# LcsNodes-Extension-BreadBoard-B_00_01.net
KiCad netlist of a schematic drawn in EasyEDA
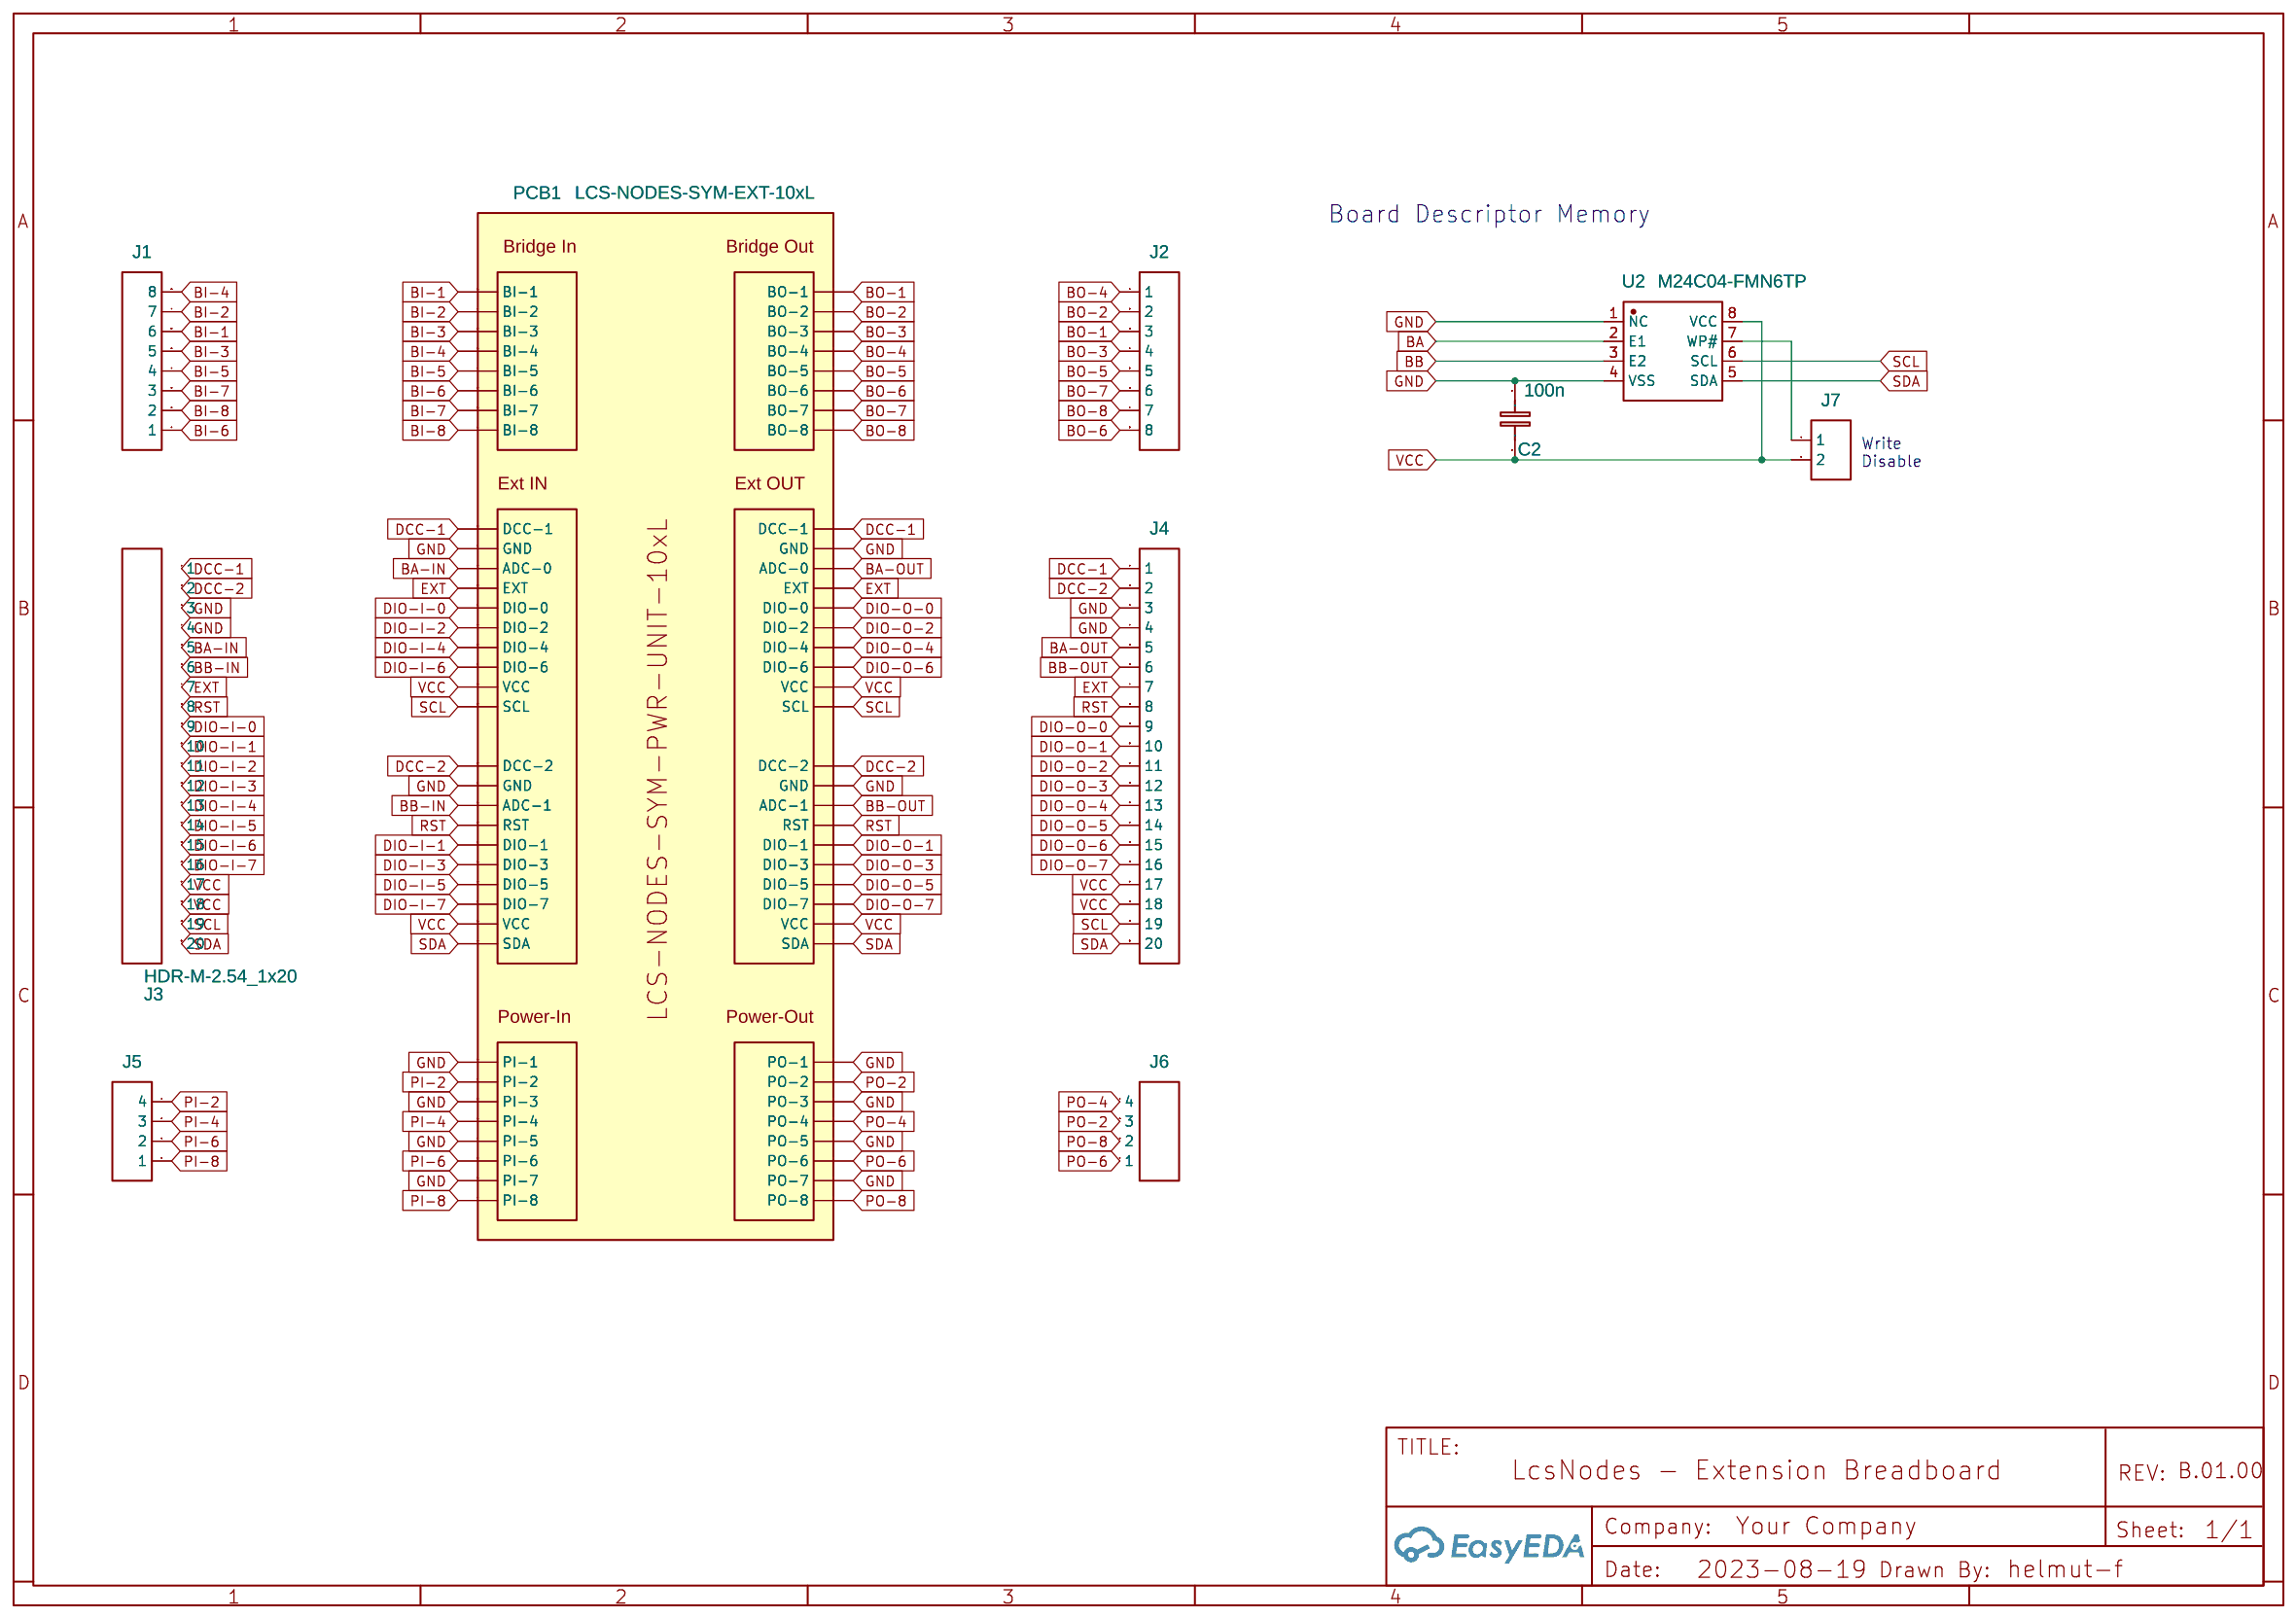
[diagram p0: schematic sheet]

(export (version "E")
  (design (tool "Eeschema 10.0.6"))
  (components
    (comp (ref "C2") (value "100n") (libsource (lib "") (part "C_0603_EU")))
    (comp (ref "J1") (value "HDR-M-2.54_1x8") (libsource (lib "") (part "HDR-M-2.54_1x8_1")))
    (comp (ref "J2") (value "HDR-M-2.54_1x8") (libsource (lib "") (part "HDR-M-2.54_1x8")))
    (comp (ref "J3") (value "HDR-M-2.54_1x20") (libsource (lib "") (part "HDR-M-2.54_1x20")))
    (comp (ref "J4") (value "HDR-M-2.54_1x20") (libsource (lib "") (part "HDR-M-2.54_1x20_1")))
    (comp (ref "J5") (value "HDR-M-2.54_1x4") (libsource (lib "") (part "HDR-M-2.54_1x4")))
    (comp (ref "J6") (value "HDR-M-2.54_1x4") (libsource (lib "") (part "HDR-M-2.54_1x4_1")))
    (comp (ref "J7") (value "HDR-M-2.54_1x2") (libsource (lib "") (part "HDR-M-2.54_1x2")))
    (comp (ref "PCB1") (value "LCS-NODES-SYM-EXT-10xL") (libsource (lib "") (part "LCS-NODES-SYM-EXT-10X8")))
    (comp (ref "U2")
      (value "M24C04-FMN6TP")
      (fields (field (name "Manufacturer") "ST(意法半导体)"))
      (libsource (lib "") (part "M24C04-FMN6TP"))
    )
  )
  (nets
    (net (code "1") (name "BA") (class "Default")
      (node (ref "U2") (pin "2") (pinfunction "E1_2") (pintype "unspecified"))
    )
    (net (code "2") (name "BA-IN") (class "Default")
      (node (ref "J3") (pin "5") (pinfunction "5_5") (pintype "unspecified"))
      (node (ref "PCB1") (pin "22") (pinfunction "ADC-0_22") (pintype "unspecified"))
    )
    (net (code "3") (name "BA-OUT") (class "Default")
      (node (ref "J4") (pin "5") (pinfunction "5_5") (pintype "unspecified"))
      (node (ref "PCB1") (pin "62") (pinfunction "ADC-0_62") (pintype "unspecified"))
    )
    (net (code "4") (name "BB") (class "Default")
      (node (ref "U2") (pin "3") (pinfunction "E2_3") (pintype "unspecified"))
    )
    (net (code "5") (name "BB-IN") (class "Default")
      (node (ref "J3") (pin "6") (pinfunction "6_6") (pintype "unspecified"))
      (node (ref "PCB1") (pin "32") (pinfunction "ADC-1_32") (pintype "unspecified"))
    )
    (net (code "6") (name "BB-OUT") (class "Default")
      (node (ref "J4") (pin "6") (pinfunction "6_6") (pintype "unspecified"))
      (node (ref "PCB1") (pin "72") (pinfunction "ADC-1_72") (pintype "unspecified"))
    )
    (net (code "7") (name "BI-1") (class "Default")
      (node (ref "J1") (pin "6") (pinfunction "6_6") (pintype "unspecified"))
      (node (ref "PCB1") (pin "10") (pinfunction "BI-1_10") (pintype "unspecified"))
    )
    (net (code "8") (name "BI-2") (class "Default")
      (node (ref "J1") (pin "7") (pinfunction "7_7") (pintype "unspecified"))
      (node (ref "PCB1") (pin "11") (pinfunction "BI-2_11") (pintype "unspecified"))
    )
    (net (code "9") (name "BI-3") (class "Default")
      (node (ref "J1") (pin "5") (pinfunction "5_5") (pintype "unspecified"))
      (node (ref "PCB1") (pin "12") (pinfunction "BI-3_12") (pintype "unspecified"))
    )
    (net (code "10") (name "BI-4") (class "Default")
      (node (ref "J1") (pin "8") (pinfunction "8_8") (pintype "unspecified"))
      (node (ref "PCB1") (pin "13") (pinfunction "BI-4_13") (pintype "unspecified"))
    )
    (net (code "11") (name "BI-5") (class "Default")
      (node (ref "J1") (pin "4") (pinfunction "4_4") (pintype "unspecified"))
      (node (ref "PCB1") (pin "14") (pinfunction "BI-5_14") (pintype "unspecified"))
    )
    (net (code "12") (name "BI-6") (class "Default")
      (node (ref "J1") (pin "1") (pinfunction "1_1") (pintype "unspecified"))
      (node (ref "PCB1") (pin "15") (pinfunction "BI-6_15") (pintype "unspecified"))
    )
    (net (code "13") (name "BI-7") (class "Default")
      (node (ref "J1") (pin "3") (pinfunction "3_3") (pintype "unspecified"))
      (node (ref "PCB1") (pin "16") (pinfunction "BI-7_16") (pintype "unspecified"))
    )
    (net (code "14") (name "BI-8") (class "Default")
      (node (ref "J1") (pin "2") (pinfunction "2_2") (pintype "unspecified"))
      (node (ref "PCB1") (pin "17") (pinfunction "BI-8_17") (pintype "unspecified"))
    )
    (net (code "15") (name "BO-1") (class "Default")
      (node (ref "J2") (pin "3") (pinfunction "3_3") (pintype "unspecified"))
      (node (ref "PCB1") (pin "50") (pinfunction "BO-1_50") (pintype "unspecified"))
    )
    (net (code "16") (name "BO-2") (class "Default")
      (node (ref "J2") (pin "2") (pinfunction "2_2") (pintype "unspecified"))
      (node (ref "PCB1") (pin "51") (pinfunction "BO-2_51") (pintype "unspecified"))
    )
    (net (code "17") (name "BO-3") (class "Default")
      (node (ref "J2") (pin "4") (pinfunction "4_4") (pintype "unspecified"))
      (node (ref "PCB1") (pin "52") (pinfunction "BO-3_52") (pintype "unspecified"))
    )
    (net (code "18") (name "BO-4") (class "Default")
      (node (ref "J2") (pin "1") (pinfunction "1_1") (pintype "unspecified"))
      (node (ref "PCB1") (pin "53") (pinfunction "BO-4_53") (pintype "unspecified"))
    )
    (net (code "19") (name "BO-5") (class "Default")
      (node (ref "J2") (pin "5") (pinfunction "5_5") (pintype "unspecified"))
      (node (ref "PCB1") (pin "54") (pinfunction "BO-5_54") (pintype "unspecified"))
    )
    (net (code "20") (name "BO-6") (class "Default")
      (node (ref "J2") (pin "8") (pinfunction "8_8") (pintype "unspecified"))
      (node (ref "PCB1") (pin "55") (pinfunction "BO-6_55") (pintype "unspecified"))
    )
    (net (code "21") (name "BO-7") (class "Default")
      (node (ref "J2") (pin "6") (pinfunction "6_6") (pintype "unspecified"))
      (node (ref "PCB1") (pin "56") (pinfunction "BO-7_56") (pintype "unspecified"))
    )
    (net (code "22") (name "BO-8") (class "Default")
      (node (ref "J2") (pin "7") (pinfunction "7_7") (pintype "unspecified"))
      (node (ref "PCB1") (pin "57") (pinfunction "BO-8_57") (pintype "unspecified"))
    )
    (net (code "23") (name "DCC-1") (class "Default")
      (node (ref "J3") (pin "1") (pinfunction "1_1") (pintype "unspecified"))
      (node (ref "J4") (pin "1") (pinfunction "1_1") (pintype "unspecified"))
      (node (ref "PCB1") (pin "20") (pinfunction "DCC-1_20") (pintype "unspecified"))
      (node (ref "PCB1") (pin "60") (pinfunction "DCC-1_60") (pintype "unspecified"))
    )
    (net (code "24") (name "DCC-2") (class "Default")
      (node (ref "J3") (pin "2") (pinfunction "2_2") (pintype "unspecified"))
      (node (ref "J4") (pin "2") (pinfunction "2_2") (pintype "unspecified"))
      (node (ref "PCB1") (pin "30") (pinfunction "DCC-2_30") (pintype "unspecified"))
      (node (ref "PCB1") (pin "70") (pinfunction "DCC-2_70") (pintype "unspecified"))
    )
    (net (code "25") (name "DIO-I-0") (class "Default")
      (node (ref "J3") (pin "9") (pinfunction "9_9") (pintype "unspecified"))
      (node (ref "PCB1") (pin "24") (pinfunction "DIO-0_24") (pintype "unspecified"))
    )
    (net (code "26") (name "DIO-I-1") (class "Default")
      (node (ref "J3") (pin "10") (pinfunction "10_10") (pintype "unspecified"))
      (node (ref "PCB1") (pin "34") (pinfunction "DIO-1_34") (pintype "unspecified"))
    )
    (net (code "27") (name "DIO-I-2") (class "Default")
      (node (ref "J3") (pin "11") (pinfunction "11_11") (pintype "unspecified"))
      (node (ref "PCB1") (pin "25") (pinfunction "DIO-2_25") (pintype "unspecified"))
    )
    (net (code "28") (name "DIO-I-3") (class "Default")
      (node (ref "J3") (pin "12") (pinfunction "12_12") (pintype "unspecified"))
      (node (ref "PCB1") (pin "35") (pinfunction "DIO-3_35") (pintype "unspecified"))
    )
    (net (code "29") (name "DIO-I-4") (class "Default")
      (node (ref "J3") (pin "13") (pinfunction "13_13") (pintype "unspecified"))
      (node (ref "PCB1") (pin "26") (pinfunction "DIO-4_26") (pintype "unspecified"))
    )
    (net (code "30") (name "DIO-I-5") (class "Default")
      (node (ref "J3") (pin "14") (pinfunction "14_14") (pintype "unspecified"))
      (node (ref "PCB1") (pin "36") (pinfunction "DIO-5_36") (pintype "unspecified"))
    )
    (net (code "31") (name "DIO-I-6") (class "Default")
      (node (ref "J3") (pin "15") (pinfunction "15_15") (pintype "unspecified"))
      (node (ref "PCB1") (pin "27") (pinfunction "DIO-6_27") (pintype "unspecified"))
    )
    (net (code "32") (name "DIO-I-7") (class "Default")
      (node (ref "J3") (pin "16") (pinfunction "16_16") (pintype "unspecified"))
      (node (ref "PCB1") (pin "37") (pinfunction "DIO-7_37") (pintype "unspecified"))
    )
    (net (code "33") (name "DIO-O-0") (class "Default")
      (node (ref "J4") (pin "9") (pinfunction "9_9") (pintype "unspecified"))
      (node (ref "PCB1") (pin "64") (pinfunction "DIO-0_64") (pintype "unspecified"))
    )
    (net (code "34") (name "DIO-O-1") (class "Default")
      (node (ref "J4") (pin "10") (pinfunction "10_10") (pintype "unspecified"))
      (node (ref "PCB1") (pin "74") (pinfunction "DIO-1_74") (pintype "unspecified"))
    )
    (net (code "35") (name "DIO-O-2") (class "Default")
      (node (ref "J4") (pin "11") (pinfunction "11_11") (pintype "unspecified"))
      (node (ref "PCB1") (pin "65") (pinfunction "DIO-2_65") (pintype "unspecified"))
    )
    (net (code "36") (name "DIO-O-3") (class "Default")
      (node (ref "J4") (pin "12") (pinfunction "12_12") (pintype "unspecified"))
      (node (ref "PCB1") (pin "75") (pinfunction "DIO-3_75") (pintype "unspecified"))
    )
    (net (code "37") (name "DIO-O-4") (class "Default")
      (node (ref "J4") (pin "13") (pinfunction "13_13") (pintype "unspecified"))
      (node (ref "PCB1") (pin "66") (pinfunction "DIO-4_66") (pintype "unspecified"))
    )
    (net (code "38") (name "DIO-O-5") (class "Default")
      (node (ref "J4") (pin "14") (pinfunction "14_14") (pintype "unspecified"))
      (node (ref "PCB1") (pin "76") (pinfunction "DIO-5_76") (pintype "unspecified"))
    )
    (net (code "39") (name "DIO-O-6") (class "Default")
      (node (ref "J4") (pin "15") (pinfunction "15_15") (pintype "unspecified"))
      (node (ref "PCB1") (pin "67") (pinfunction "DIO-6_67") (pintype "unspecified"))
    )
    (net (code "40") (name "DIO-O-7") (class "Default")
      (node (ref "J4") (pin "16") (pinfunction "16_16") (pintype "unspecified"))
      (node (ref "PCB1") (pin "77") (pinfunction "DIO-7_77") (pintype "unspecified"))
    )
    (net (code "41") (name "EXT") (class "Default")
      (node (ref "J3") (pin "7") (pinfunction "7_7") (pintype "unspecified"))
      (node (ref "J4") (pin "7") (pinfunction "7_7") (pintype "unspecified"))
      (node (ref "PCB1") (pin "23") (pinfunction "EXT_23") (pintype "unspecified"))
      (node (ref "PCB1") (pin "63") (pinfunction "EXT_63") (pintype "unspecified"))
    )
    (net (code "42") (name "GND") (class "Default")
      (node (ref "C2") (pin "1") (pinfunction "1_1") (pintype "unspecified"))
      (node (ref "J3") (pin "3") (pinfunction "3_3") (pintype "unspecified"))
      (node (ref "J3") (pin "4") (pinfunction "4_4") (pintype "unspecified"))
      (node (ref "J4") (pin "3") (pinfunction "3_3") (pintype "unspecified"))
      (node (ref "J4") (pin "4") (pinfunction "4_4") (pintype "unspecified"))
      (node (ref "PCB1") (pin "21") (pinfunction "GND_21") (pintype "unspecified"))
      (node (ref "PCB1") (pin "31") (pinfunction "GND_31") (pintype "unspecified"))
      (node (ref "PCB1") (pin "40") (pinfunction "PI-1_40") (pintype "unspecified"))
      (node (ref "PCB1") (pin "42") (pinfunction "PI-3_42") (pintype "unspecified"))
      (node (ref "PCB1") (pin "44") (pinfunction "PI-5_44") (pintype "unspecified"))
      (node (ref "PCB1") (pin "46") (pinfunction "PI-7_46") (pintype "unspecified"))
      (node (ref "PCB1") (pin "61") (pinfunction "GND_61") (pintype "unspecified"))
      (node (ref "PCB1") (pin "71") (pinfunction "GND_71") (pintype "unspecified"))
      (node (ref "PCB1") (pin "80") (pinfunction "PO-1_80") (pintype "unspecified"))
      (node (ref "PCB1") (pin "82") (pinfunction "PO-3_82") (pintype "unspecified"))
      (node (ref "PCB1") (pin "84") (pinfunction "PO-5_84") (pintype "unspecified"))
      (node (ref "PCB1") (pin "86") (pinfunction "PO-7_86") (pintype "unspecified"))
      (node (ref "U2") (pin "1") (pinfunction "NC_1") (pintype "unspecified"))
      (node (ref "U2") (pin "4") (pinfunction "VSS_4") (pintype "unspecified"))
    )
    (net (code "43") (name "Net-(U2-WP#)") (class "Default")
      (node (ref "J7") (pin "1") (pinfunction "1_1") (pintype "unspecified"))
      (node (ref "U2") (pin "7") (pinfunction "WP#_7") (pintype "unspecified"))
    )
    (net (code "44") (name "PI-2") (class "Default")
      (node (ref "J5") (pin "4") (pinfunction "4_4") (pintype "unspecified"))
      (node (ref "PCB1") (pin "41") (pinfunction "PI-2_41") (pintype "unspecified"))
    )
    (net (code "45") (name "PI-4") (class "Default")
      (node (ref "J5") (pin "3") (pinfunction "3_3") (pintype "unspecified"))
      (node (ref "PCB1") (pin "43") (pinfunction "PI-4_43") (pintype "unspecified"))
    )
    (net (code "46") (name "PI-6") (class "Default")
      (node (ref "J5") (pin "2") (pinfunction "2_2") (pintype "unspecified"))
      (node (ref "PCB1") (pin "45") (pinfunction "PI-6_45") (pintype "unspecified"))
    )
    (net (code "47") (name "PI-8") (class "Default")
      (node (ref "J5") (pin "1") (pinfunction "1_1") (pintype "unspecified"))
      (node (ref "PCB1") (pin "47") (pinfunction "PI-8_47") (pintype "unspecified"))
    )
    (net (code "48") (name "PO-2") (class "Default")
      (node (ref "J6") (pin "3") (pinfunction "3_3") (pintype "unspecified"))
      (node (ref "PCB1") (pin "81") (pinfunction "PO-2_81") (pintype "unspecified"))
    )
    (net (code "49") (name "PO-4") (class "Default")
      (node (ref "J6") (pin "4") (pinfunction "4_4") (pintype "unspecified"))
      (node (ref "PCB1") (pin "83") (pinfunction "PO-4_83") (pintype "unspecified"))
    )
    (net (code "50") (name "PO-6") (class "Default")
      (node (ref "J6") (pin "1") (pinfunction "1_1") (pintype "unspecified"))
      (node (ref "PCB1") (pin "85") (pinfunction "PO-6_85") (pintype "unspecified"))
    )
    (net (code "51") (name "PO-8") (class "Default")
      (node (ref "J6") (pin "2") (pinfunction "2_2") (pintype "unspecified"))
      (node (ref "PCB1") (pin "87") (pinfunction "PO-8_87") (pintype "unspecified"))
    )
    (net (code "52") (name "RST") (class "Default")
      (node (ref "J3") (pin "8") (pinfunction "8_8") (pintype "unspecified"))
      (node (ref "J4") (pin "8") (pinfunction "8_8") (pintype "unspecified"))
      (node (ref "PCB1") (pin "33") (pinfunction "RST_33") (pintype "unspecified"))
      (node (ref "PCB1") (pin "73") (pinfunction "RST_73") (pintype "unspecified"))
    )
    (net (code "53") (name "SCL") (class "Default")
      (node (ref "J3") (pin "19") (pinfunction "19_19") (pintype "unspecified"))
      (node (ref "J4") (pin "19") (pinfunction "19_19") (pintype "unspecified"))
      (node (ref "PCB1") (pin "29") (pinfunction "SCL_29") (pintype "unspecified"))
      (node (ref "PCB1") (pin "69") (pinfunction "SCL_69") (pintype "unspecified"))
      (node (ref "U2") (pin "6") (pinfunction "SCL_6") (pintype "unspecified"))
    )
    (net (code "54") (name "SDA") (class "Default")
      (node (ref "J3") (pin "20") (pinfunction "20_20") (pintype "unspecified"))
      (node (ref "J4") (pin "20") (pinfunction "20_20") (pintype "unspecified"))
      (node (ref "PCB1") (pin "39") (pinfunction "SDA_39") (pintype "unspecified"))
      (node (ref "PCB1") (pin "79") (pinfunction "SDA_79") (pintype "unspecified"))
      (node (ref "U2") (pin "5") (pinfunction "SDA_5") (pintype "unspecified"))
    )
    (net (code "55") (name "VCC") (class "Default")
      (node (ref "C2") (pin "2") (pinfunction "2_2") (pintype "unspecified"))
      (node (ref "J3") (pin "17") (pinfunction "17_17") (pintype "unspecified"))
      (node (ref "J3") (pin "18") (pinfunction "18_18") (pintype "unspecified"))
      (node (ref "J4") (pin "17") (pinfunction "17_17") (pintype "unspecified"))
      (node (ref "J4") (pin "18") (pinfunction "18_18") (pintype "unspecified"))
      (node (ref "J7") (pin "2") (pinfunction "2_2") (pintype "unspecified"))
      (node (ref "PCB1") (pin "28") (pinfunction "VCC_28") (pintype "unspecified"))
      (node (ref "PCB1") (pin "38") (pinfunction "VCC_38") (pintype "unspecified"))
      (node (ref "PCB1") (pin "68") (pinfunction "VCC_68") (pintype "unspecified"))
      (node (ref "PCB1") (pin "78") (pinfunction "VCC_78") (pintype "unspecified"))
      (node (ref "U2") (pin "8") (pinfunction "VCC_8") (pintype "unspecified"))
    )
  )
)
